# Joshi_Sanskriti.net
KiCad netlist of a schematic drawn in EAGLE
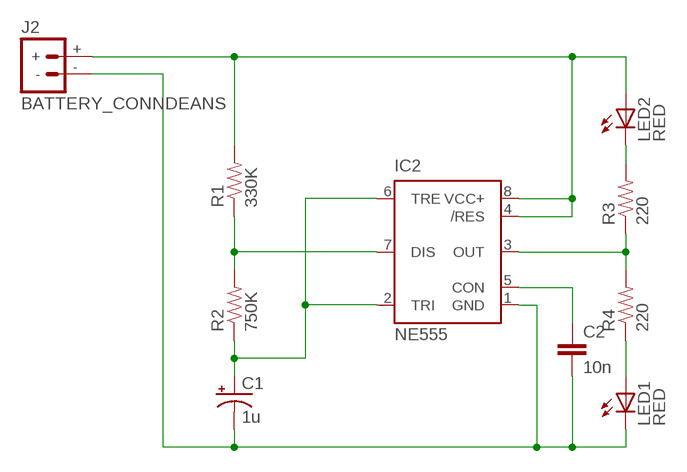
[diagram p0: schematic, sheet 1]

(export (version "E")
  (design (tool "Eeschema 10.0.6"))
  (components
    (comp (ref "C1")
      (value "1u")
      (footprint "eagle-import:CPOL-RADIAL-10UF-25V")
      (libsource (lib "eagle-import") (part "CAP_POLPTH2"))
    )
    (comp (ref "C2")
      (value "10n")
      (footprint "eagle-import:CAP-PTH-SMALL")
      (libsource (lib "eagle-import") (part "CAPPTH"))
    )
    (comp (ref "IC2")
      (value "NE555")
      (footprint "eagle-import:DIL-08")
      (fields (field (name "MF") "Arrow Electronics") (field (name "MPN") "NE555N"))
      (libsource (lib "eagle-import") (part "NE555"))
    )
    (comp (ref "J2")
      (value "BATTERY_CONNDEANS")
      (footprint "eagle-import:DEANS")
      (libsource (lib "eagle-import") (part "BATTERY_CONNDEANS"))
    )
    (comp (ref "LED1")
      (value "RED")
      (footprint "eagle-import:LED5MM")
      (libsource (lib "eagle-import") (part "LED5MM"))
    )
    (comp (ref "LED2")
      (value "RED")
      (footprint "eagle-import:LED5MM")
      (libsource (lib "eagle-import") (part "LED5MM"))
    )
    (comp (ref "R1")
      (value "330K")
      (footprint "eagle-import:AXIAL-0.3")
      (libsource (lib "eagle-import") (part "RESISTORAXIAL-0.3"))
    )
    (comp (ref "R2")
      (value "750K")
      (footprint "eagle-import:AXIAL-0.3")
      (libsource (lib "eagle-import") (part "RESISTORAXIAL-0.3"))
    )
    (comp (ref "R3")
      (value "220")
      (footprint "eagle-import:AXIAL-0.3")
      (libsource (lib "eagle-import") (part "RESISTORAXIAL-0.3"))
    )
    (comp (ref "R4")
      (value "220")
      (footprint "eagle-import:AXIAL-0.3")
      (libsource (lib "eagle-import") (part "RESISTORAXIAL-0.3"))
    )
  )
  (nets
    (net (code "1") (name "Net-(C1-+)") (class "Default")
      (node (ref "C1") (pin "1") (pinfunction "+_1") (pintype "passive"))
      (node (ref "IC2") (pin "2") (pinfunction "TRI_2") (pintype "input"))
      (node (ref "IC2") (pin "6") (pinfunction "TRE_6") (pintype "input"))
      (node (ref "R2") (pin "P$1") (pinfunction "1_P$1") (pintype "passive"))
    )
    (net (code "2") (name "Net-(C1--)") (class "Default")
      (node (ref "C1") (pin "2") (pinfunction "-_2") (pintype "passive"))
      (node (ref "C2") (pin "2") (pinfunction "2_2") (pintype "passive"))
      (node (ref "IC2") (pin "1") (pinfunction "GND_1") (pintype "power_in"))
      (node (ref "J2") (pin "-") (pinfunction "-_-") (pintype "passive"))
      (node (ref "LED1") (pin "K") (pinfunction "C_K") (pintype "passive"))
    )
    (net (code "3") (name "Net-(IC2-CON)") (class "Default")
      (node (ref "C2") (pin "1") (pinfunction "1_1") (pintype "passive"))
      (node (ref "IC2") (pin "5") (pinfunction "CON_5") (pintype "input"))
    )
    (net (code "4") (name "Net-(IC2-DIS)") (class "Default")
      (node (ref "IC2") (pin "7") (pinfunction "DIS_7") (pintype "input"))
      (node (ref "R1") (pin "P$1") (pinfunction "1_P$1") (pintype "passive"))
      (node (ref "R2") (pin "P$2") (pinfunction "2_P$2") (pintype "passive"))
    )
    (net (code "5") (name "Net-(IC2-OUT)") (class "Default")
      (node (ref "IC2") (pin "3") (pinfunction "OUT_3") (pintype "output"))
      (node (ref "R3") (pin "P$1") (pinfunction "1_P$1") (pintype "passive"))
      (node (ref "R4") (pin "P$2") (pinfunction "2_P$2") (pintype "passive"))
    )
    (net (code "6") (name "Net-(IC2-VCC+)") (class "Default")
      (node (ref "IC2") (pin "4") (pinfunction "/RES_4") (pintype "input"))
      (node (ref "IC2") (pin "8") (pinfunction "VCC+_8") (pintype "power_in"))
      (node (ref "J2") (pin "+") (pinfunction "+_+") (pintype "passive"))
      (node (ref "LED2") (pin "A") (pinfunction "A_A") (pintype "passive"))
      (node (ref "R1") (pin "P$2") (pinfunction "2_P$2") (pintype "passive"))
    )
    (net (code "7") (name "Net-(LED2-C)") (class "Default")
      (node (ref "LED2") (pin "K") (pinfunction "C_K") (pintype "passive"))
      (node (ref "R3") (pin "P$2") (pinfunction "2_P$2") (pintype "passive"))
    )
    (net (code "8") (name "Net-(R4-1)") (class "Default")
      (node (ref "LED1") (pin "A") (pinfunction "A_A") (pintype "passive"))
      (node (ref "R4") (pin "P$1") (pinfunction "1_P$1") (pintype "passive"))
    )
  )
)
